# Smart_Switch.net
KiCad netlist of a schematic drawn in EAGLE
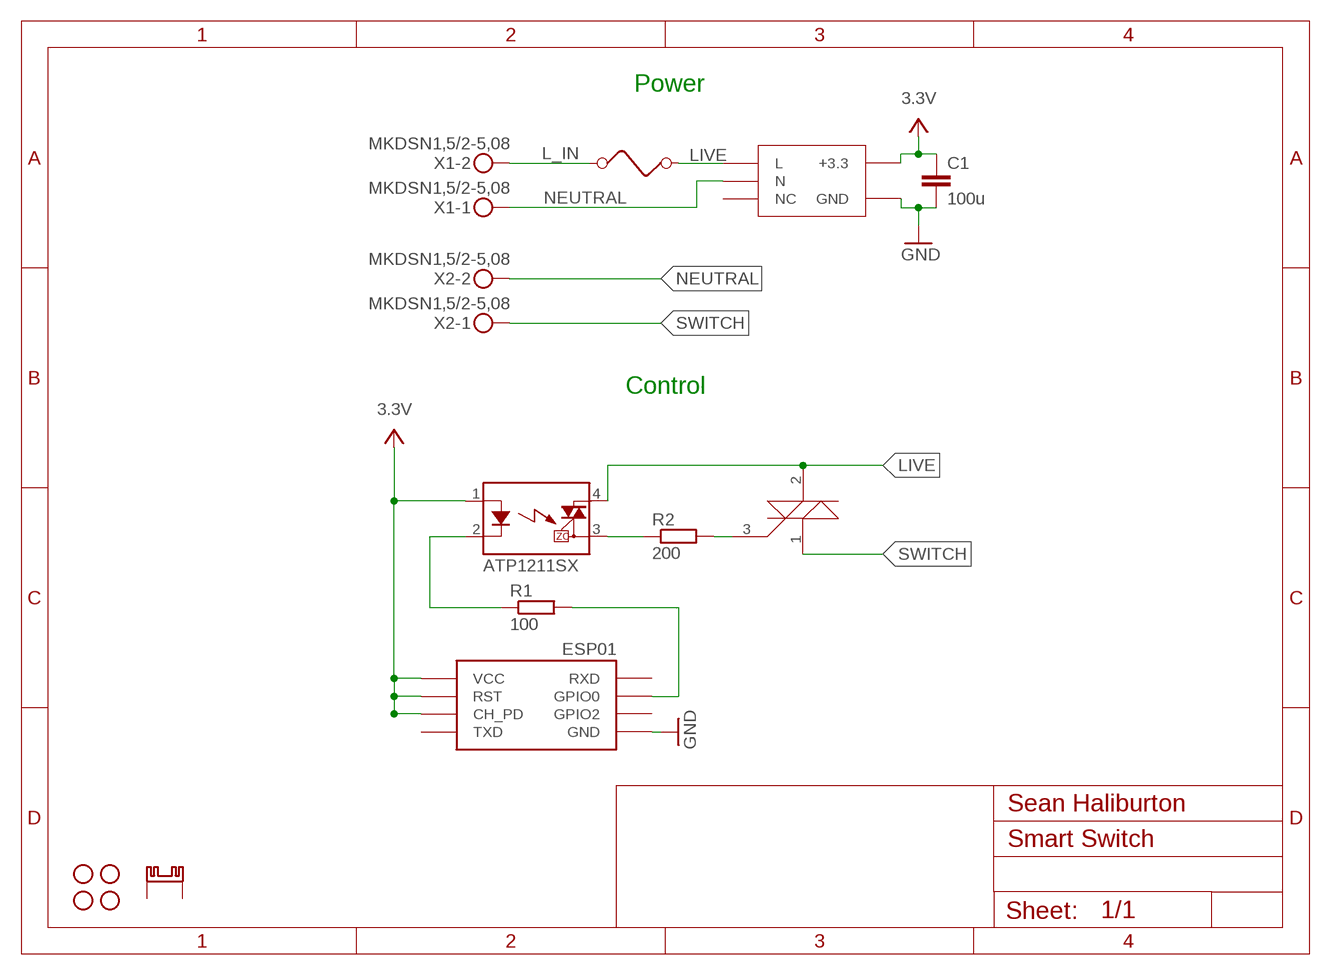
[diagram p0: schematic, sheet 1]

(export (version "E")
  (design (tool "Eeschema 10.0.6"))
  (components
    (comp (ref "C1")
      (value "100u")
      (footprint "eagle-import:C0805")
      (libsource (lib "eagle-import") (part "C-EUC0805"))
    )
    (comp (ref "H1")
      (value "STAND-OFF")
      (footprint "eagle-import:STAND-OFF")
      (libsource (lib "eagle-import") (part "STAND-OFF"))
    )
    (comp (ref "H2")
      (value "STAND-OFF")
      (footprint "eagle-import:STAND-OFF")
      (libsource (lib "eagle-import") (part "STAND-OFF"))
    )
    (comp (ref "H3")
      (value "STAND-OFF")
      (footprint "eagle-import:STAND-OFF")
      (libsource (lib "eagle-import") (part "STAND-OFF"))
    )
    (comp (ref "H4")
      (value "STAND-OFF")
      (footprint "eagle-import:STAND-OFF")
      (libsource (lib "eagle-import") (part "STAND-OFF"))
    )
    (comp (ref "K1")
      (value "ATP1211SX")
      (footprint "eagle-import:SOP04")
      (libsource (lib "eagle-import") (part "ATP1211SX"))
    )
    (comp (ref "R1")
      (value "100")
      (footprint "eagle-import:R0805")
      (libsource (lib "eagle-import") (part "R-EU_R0805"))
    )
    (comp (ref "R2")
      (value "200")
      (footprint "eagle-import:R0805")
      (libsource (lib "eagle-import") (part "R-EU_R0805"))
    )
    (comp (ref "U$1")
      (value "ESP01")
      (footprint "eagle-import:ESP01")
      (libsource (lib "eagle-import") (part "ESP01"))
    )
    (comp (ref "U$2")
      (value "RAC04-GB")
      (footprint "eagle-import:RAC04-GB")
      (libsource (lib "eagle-import") (part "RAC04-GB"))
    )
    (comp (ref "U$3")
      (value "BTA16")
      (footprint "eagle-import:TO220V")
      (libsource (lib "eagle-import") (part "BTA16"))
    )
    (comp (ref "U$4")
      (value "FUSE")
      (footprint "eagle-import:FUSE")
      (libsource (lib "eagle-import") (part "FUSE"))
    )
    (comp (ref "U$5")
      (value "RA-T2X-38E")
      (footprint "eagle-import:SK129")
      (libsource (lib "eagle-import") (part "RA-T2X-38E"))
    )
    (comp (ref "X1")
      (value "MKDSN1,5/2-5,08")
      (footprint "eagle-import:MKDSN1,5_2-5,08")
      (libsource (lib "eagle-import") (part "MKDSN1,5/2-5,08"))
    )
    (comp (ref "X2")
      (value "MKDSN1,5/2-5,08")
      (footprint "eagle-import:MKDSN1,5_2-5,08")
      (libsource (lib "eagle-import") (part "MKDSN1,5/2-5,08"))
    )
  )
  (nets
    (net (code "1") (name "/L_IN") (class "Default")
      (node (ref "U$4") (pin "P$1") (pinfunction "1_P$1") (pintype "passive"))
      (node (ref "X1") (pin "2") (pinfunction "KL_2") (pintype "passive"))
    )
    (net (code "2") (name "3.3V") (class "Default")
      (node (ref "C1") (pin "1") (pinfunction "1_1") (pintype "passive"))
      (node (ref "K1") (pin "1") (pinfunction "A_1") (pintype "passive"))
      (node (ref "U$1") (pin "CH_PD") (pinfunction "CH_PD_CH_PD") (pintype "bidirectional"))
      (node (ref "U$1") (pin "RST") (pinfunction "RST_RST") (pintype "bidirectional"))
      (node (ref "U$1") (pin "VCC") (pinfunction "VCC_VCC") (pintype "bidirectional"))
      (node (ref "U$2") (pin "3.3") (pinfunction "+3.3_3.3") (pintype "bidirectional"))
    )
    (net (code "3") (name "GND") (class "Default")
      (node (ref "C1") (pin "2") (pinfunction "2_2") (pintype "passive"))
      (node (ref "U$1") (pin "GND") (pinfunction "GND_GND") (pintype "bidirectional"))
      (node (ref "U$2") (pin "GND") (pinfunction "GND_GND") (pintype "bidirectional"))
    )
    (net (code "4") (name "LIVE") (class "Default")
      (node (ref "K1") (pin "4") (pinfunction "DS1_4") (pintype "passive"))
      (node (ref "U$2") (pin "L") (pinfunction "L_L") (pintype "bidirectional"))
      (node (ref "U$3") (pin "2") (pinfunction "A2_2") (pintype "bidirectional"))
      (node (ref "U$4") (pin "P$2") (pinfunction "2_P$2") (pintype "passive"))
    )
    (net (code "5") (name "NEUTRAL") (class "Default")
      (node (ref "U$2") (pin "N") (pinfunction "N_N") (pintype "bidirectional"))
      (node (ref "X1") (pin "1") (pinfunction "KL_1") (pintype "passive"))
      (node (ref "X2") (pin "2") (pinfunction "KL_2") (pintype "passive"))
    )
    (net (code "6") (name "Net-(K1-DS2)") (class "Default")
      (node (ref "K1") (pin "3") (pinfunction "DS2_3") (pintype "passive"))
      (node (ref "R2") (pin "1") (pinfunction "1_1") (pintype "passive"))
    )
    (net (code "7") (name "Net-(K1-K)") (class "Default")
      (node (ref "K1") (pin "2") (pinfunction "K_2") (pintype "passive"))
      (node (ref "R1") (pin "1") (pinfunction "1_1") (pintype "passive"))
    )
    (net (code "8") (name "Net-(R1-Pad2)") (class "Default")
      (node (ref "R1") (pin "2") (pinfunction "2_2") (pintype "passive"))
      (node (ref "U$1") (pin "GPIO0") (pinfunction "GPIO0_GPIO0") (pintype "bidirectional"))
    )
    (net (code "9") (name "Net-(U$3-G)") (class "Default")
      (node (ref "R2") (pin "2") (pinfunction "2_2") (pintype "passive"))
      (node (ref "U$3") (pin "3") (pinfunction "G_3") (pintype "input"))
    )
    (net (code "10") (name "SWITCH") (class "Default")
      (node (ref "U$3") (pin "1") (pinfunction "A1_1") (pintype "bidirectional"))
      (node (ref "X2") (pin "1") (pinfunction "KL_1") (pintype "passive"))
    )
    (net (code "11") (name "unconnected-(U$1-PadGPIO2)") (class "Default")
      (node (ref "U$1") (pin "GPIO2") (pinfunction "GPIO2_GPIO2") (pintype "bidirectional"))
    )
    (net (code "12") (name "unconnected-(U$1-RXD-PadRX)") (class "Default")
      (node (ref "U$1") (pin "RX") (pinfunction "RXD_RX") (pintype "bidirectional"))
    )
    (net (code "13") (name "unconnected-(U$1-TXD-PadTX)") (class "Default")
      (node (ref "U$1") (pin "TX") (pinfunction "TXD_TX") (pintype "bidirectional"))
    )
    (net (code "14") (name "unconnected-(U$2-PadNC)") (class "Default")
      (node (ref "U$2") (pin "NC") (pinfunction "NC_NC") (pintype "bidirectional"))
    )
    (net (code "15") (name "unconnected-(U$5-P$1-PadA2,5)") (class "Default")
      (node (ref "U$5") (pin "A2,5") (pinfunction "P$1_A2,5") (pintype "bidirectional"))
    )
    (net (code "16") (name "unconnected-(U$5-P$2-PadB2,5)") (class "Default")
      (node (ref "U$5") (pin "B2,5") (pinfunction "P$2_B2,5") (pintype "bidirectional"))
    )
  )
)
